# untitled.net
KiCad netlist of a schematic drawn in EAGLE
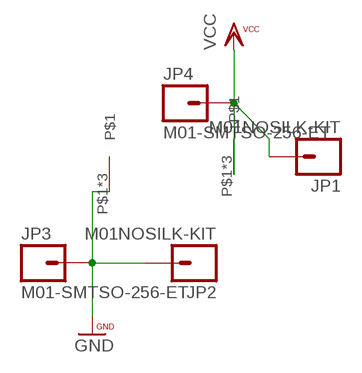
[diagram p0: schematic, sheet 1]

(export (version "E")
  (design (tool "Eeschema 10.0.6"))
  (components
    (comp (ref "JP1")
      (value "M01NOSILK-KIT")
      (footprint "eagle-import:1X01NS-KIT")
      (libsource (lib "eagle-import") (part "M01NOSILK-KIT"))
    )
    (comp (ref "JP2")
      (value "M01NOSILK-KIT")
      (footprint "eagle-import:1X01NS-KIT")
      (libsource (lib "eagle-import") (part "M01NOSILK-KIT"))
    )
    (comp (ref "JP3")
      (value "M01-SMTSO-256-ET")
      (footprint "eagle-import:SMTSO-256-ET")
      (libsource (lib "eagle-import") (part "M01-SMTSO-256-ET"))
    )
    (comp (ref "JP4")
      (value "M01-SMTSO-256-ET")
      (footprint "eagle-import:SMTSO-256-ET")
      (libsource (lib "eagle-import") (part "M01-SMTSO-256-ET"))
    )
    (comp (ref "U$1")
      (value "PANTOGRAPH")
      (footprint "eagle-import:WIREHOLDER")
      (libsource (lib "eagle-import") (part "PANTOGRAPH"))
    )
    (comp (ref "U$2")
      (value "PANTOGRAPH")
      (footprint "eagle-import:WIREHOLDER")
      (libsource (lib "eagle-import") (part "PANTOGRAPH"))
    )
  )
  (nets
    (net (code "1") (name "GND") (class "Default")
      (node (ref "JP2") (pin "1") (pinfunction "1_1") (pintype "passive"))
      (node (ref "JP3") (pin "P$1") (pinfunction "1_P$1") (pintype "passive"))
      (node (ref "U$1") (pin "P$1") (pinfunction "P$1_P$1") (pintype "bidirectional"))
      (node (ref "U$1") (pin "P$2") (pinfunction "P$1_P$2") (pintype "bidirectional"))
      (node (ref "U$1") (pin "P$3") (pinfunction "P$1_P$3") (pintype "bidirectional"))
    )
    (net (code "2") (name "VCC") (class "Default")
      (node (ref "JP1") (pin "1") (pinfunction "1_1") (pintype "passive"))
      (node (ref "JP4") (pin "P$1") (pinfunction "1_P$1") (pintype "passive"))
      (node (ref "U$2") (pin "P$1") (pinfunction "P$1_P$1") (pintype "bidirectional"))
      (node (ref "U$2") (pin "P$2") (pinfunction "P$1_P$2") (pintype "bidirectional"))
      (node (ref "U$2") (pin "P$3") (pinfunction "P$1_P$3") (pintype "bidirectional"))
    )
  )
)
